# shield_mega_seed4_mpu_lobo8.net
KiCad netlist of a schematic drawn in EAGLE
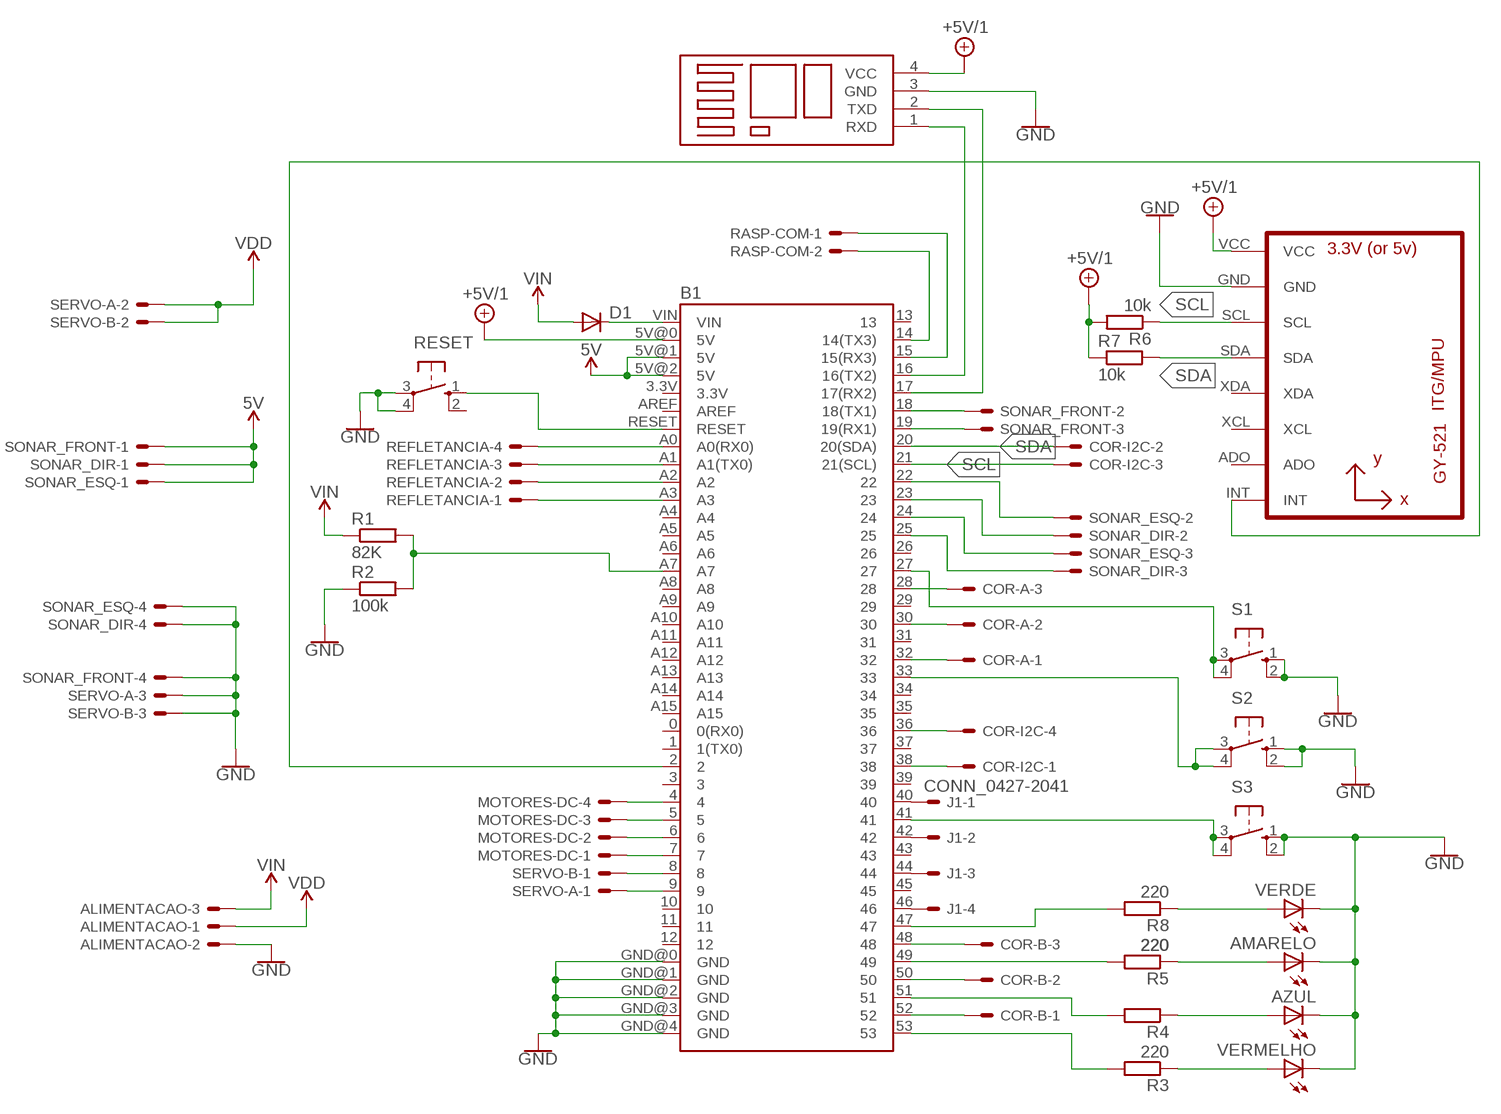
[diagram p0: schematic, sheet 1]

(export (version "E")
  (design (tool "Eeschema 10.0.6"))
  (components
    (comp (ref "ALIMENTACAO")
      (value "22-23-2031")
      (footprint "eagle-import:22-23-2031")
      (fields (field (name "MF") "MOLEX"))
      (libsource (lib "eagle-import") (part "22-23-2031"))
    )
    (comp (ref "AMARELO")
      (value "LED5MM")
      (footprint "eagle-import:LED5MM")
      (libsource (lib "eagle-import") (part "LED5MM"))
    )
    (comp (ref "AZUL")
      (value "LED5MM")
      (footprint "eagle-import:LED5MM")
      (libsource (lib "eagle-import") (part "LED5MM"))
    )
    (comp (ref "B1")
      (value "ARDUINO_MEGA_R3FULL")
      (footprint "eagle-import:ARDUINO_MEGA")
      (libsource (lib "eagle-import") (part "ARDUINO_MEGA_R3FULL"))
    )
    (comp (ref "B2")
      (value "BLUETOOTH")
      (footprint "eagle-import:BLUETOOTH")
      (libsource (lib "eagle-import") (part "BLUETOOTH"))
    )
    (comp (ref "COR-A")
      (value "22-23-2031")
      (footprint "eagle-import:22-23-2031")
      (fields (field (name "MF") "MOLEX"))
      (libsource (lib "eagle-import") (part "22-23-2031"))
    )
    (comp (ref "COR-B")
      (value "22-23-2031")
      (footprint "eagle-import:22-23-2031")
      (fields (field (name "MF") "MOLEX"))
      (libsource (lib "eagle-import") (part "22-23-2031"))
    )
    (comp (ref "COR-I2C")
      (value "22-23-2041")
      (footprint "eagle-import:22-23-2041")
      (fields (field (name "MF") "MOLEX"))
      (libsource (lib "eagle-import") (part "22-23-2041"))
    )
    (comp (ref "D1")
      (value "1N4004")
      (footprint "eagle-import:DO41-10")
      (libsource (lib "eagle-import") (part "1N4004"))
    )
    (comp (ref "J1")
      (value "CONN_0427-2041")
      (footprint "eagle-import:6410-04")
      (libsource (lib "eagle-import") (part "CONN_0427-2041"))
    )
    (comp (ref "MOTORES-DC")
      (value "22-23-2041")
      (footprint "eagle-import:22-23-2041")
      (fields (field (name "MF") "MOLEX"))
      (libsource (lib "eagle-import") (part "22-23-2041"))
    )
    (comp (ref "R1")
      (value "82K")
      (footprint "eagle-import:0204_7")
      (libsource (lib "eagle-import") (part "R-EU_0204/7"))
    )
    (comp (ref "R2")
      (value "100k")
      (footprint "eagle-import:0204_7")
      (libsource (lib "eagle-import") (part "R-EU_0204/7"))
    )
    (comp (ref "R3")
      (value "220")
      (footprint "eagle-import:0207_7")
      (libsource (lib "eagle-import") (part "R-EU_0207/7"))
    )
    (comp (ref "R4")
      (value "220")
      (footprint "eagle-import:0207_7")
      (libsource (lib "eagle-import") (part "R-EU_0207/7"))
    )
    (comp (ref "R5")
      (value "220")
      (footprint "eagle-import:0207_7")
      (libsource (lib "eagle-import") (part "R-EU_0207/7"))
    )
    (comp (ref "R6")
      (value "10k")
      (footprint "eagle-import:0204_7")
      (libsource (lib "eagle-import") (part "R-EU_0204/7"))
    )
    (comp (ref "R7")
      (value "10k")
      (footprint "eagle-import:0204_7")
      (libsource (lib "eagle-import") (part "R-EU_0204/7"))
    )
    (comp (ref "R8")
      (value "220")
      (footprint "eagle-import:0207_7")
      (libsource (lib "eagle-import") (part "R-EU_0207/7"))
    )
    (comp (ref "RASP-COM")
      (value "22-23-2021")
      (footprint "eagle-import:22-23-2021")
      (fields (field (name "MF") "MOLEX"))
      (libsource (lib "eagle-import") (part "22-23-2021"))
    )
    (comp (ref "REFLETANCIA")
      (value "22-23-2041")
      (footprint "eagle-import:22-23-2041")
      (fields (field (name "MF") "MOLEX"))
      (libsource (lib "eagle-import") (part "22-23-2041"))
    )
    (comp (ref "RESET")
      (value "10-XX")
      (footprint "eagle-import:B3F-10XX")
      (fields (field (name "MPN") "B3F-1000"))
      (libsource (lib "eagle-import") (part "10-XX"))
    )
    (comp (ref "S1")
      (value "10-XX")
      (footprint "eagle-import:B3F-10XX")
      (fields (field (name "MPN") "B3F-1000"))
      (libsource (lib "eagle-import") (part "10-XX"))
    )
    (comp (ref "S2")
      (value "10-XX")
      (footprint "eagle-import:B3F-10XX")
      (fields (field (name "MPN") "B3F-1000"))
      (libsource (lib "eagle-import") (part "10-XX"))
    )
    (comp (ref "S3")
      (value "10-XX")
      (footprint "eagle-import:B3F-10XX")
      (fields (field (name "MPN") "B3F-1000"))
      (libsource (lib "eagle-import") (part "10-XX"))
    )
    (comp (ref "SERVO-A")
      (value "22-23-2031")
      (footprint "eagle-import:22-23-2031")
      (fields (field (name "MF") "MOLEX"))
      (libsource (lib "eagle-import") (part "22-23-2031"))
    )
    (comp (ref "SERVO-B")
      (value "22-23-2031")
      (footprint "eagle-import:22-23-2031")
      (fields (field (name "MF") "MOLEX"))
      (libsource (lib "eagle-import") (part "22-23-2031"))
    )
    (comp (ref "SONAR_DIR")
      (value "22-23-2041")
      (footprint "eagle-import:22-23-2041")
      (fields (field (name "MF") "MOLEX"))
      (libsource (lib "eagle-import") (part "22-23-2041"))
    )
    (comp (ref "SONAR_ESQ")
      (value "22-23-2041")
      (footprint "eagle-import:22-23-2041")
      (fields (field (name "MF") "MOLEX"))
      (libsource (lib "eagle-import") (part "22-23-2041"))
    )
    (comp (ref "SONAR_FRONT")
      (value "22-23-2041")
      (footprint "eagle-import:22-23-2041")
      (fields (field (name "MF") "MOLEX"))
      (libsource (lib "eagle-import") (part "22-23-2041"))
    )
    (comp (ref "U1")
      (value "GY-521MPU6050")
      (footprint "eagle-import:GY-521")
      (libsource (lib "eagle-import") (part "GY-521MPU6050"))
    )
    (comp (ref "VERDE")
      (value "LED5MM")
      (footprint "eagle-import:LED5MM")
      (libsource (lib "eagle-import") (part "LED5MM"))
    )
    (comp (ref "VERMELHO")
      (value "LED5MM")
      (footprint "eagle-import:LED5MM")
      (libsource (lib "eagle-import") (part "LED5MM"))
    )
  )
  (nets
    (net (code "1") (name "+5V{slash}1") (class "Default")
      (node (ref "B1") (pin "5V@0") (pinfunction "5V_5V@0") (pintype "bidirectional"))
      (node (ref "B2") (pin "4") (pinfunction "VCC_4") (pintype "power_in"))
      (node (ref "R6") (pin "2") (pinfunction "2_2") (pintype "passive"))
      (node (ref "R7") (pin "1") (pinfunction "1_1") (pintype "passive"))
      (node (ref "U1") (pin "VCC") (pinfunction "VCC_VCC") (pintype "bidirectional"))
    )
    (net (code "2") (name "5V") (class "Default")
      (node (ref "B1") (pin "5V@1") (pinfunction "5V_5V@1") (pintype "bidirectional"))
      (node (ref "B1") (pin "5V@2") (pinfunction "5V_5V@2") (pintype "bidirectional"))
      (node (ref "SONAR_DIR") (pin "1") (pinfunction "S_1") (pintype "passive"))
      (node (ref "SONAR_ESQ") (pin "1") (pinfunction "S_1") (pintype "passive"))
      (node (ref "SONAR_FRONT") (pin "1") (pinfunction "S_1") (pintype "passive"))
    )
    (net (code "3") (name "GND") (class "Default")
      (node (ref "ALIMENTACAO") (pin "2") (pinfunction "S_2") (pintype "passive"))
      (node (ref "AMARELO") (pin "K") (pinfunction "C_K") (pintype "passive"))
      (node (ref "AZUL") (pin "K") (pinfunction "C_K") (pintype "passive"))
      (node (ref "B1") (pin "GND@0") (pinfunction "GND_GND@0") (pintype "bidirectional"))
      (node (ref "B1") (pin "GND@1") (pinfunction "GND_GND@1") (pintype "bidirectional"))
      (node (ref "B1") (pin "GND@2") (pinfunction "GND_GND@2") (pintype "bidirectional"))
      (node (ref "B1") (pin "GND@3") (pinfunction "GND_GND@3") (pintype "bidirectional"))
      (node (ref "B1") (pin "GND@4") (pinfunction "GND_GND@4") (pintype "bidirectional"))
      (node (ref "B2") (pin "3") (pinfunction "GND_3") (pintype "power_in"))
      (node (ref "R2") (pin "1") (pinfunction "1_1") (pintype "passive"))
      (node (ref "RESET") (pin "3") (pinfunction "P_3") (pintype "passive"))
      (node (ref "RESET") (pin "4") (pinfunction "P1_4") (pintype "passive"))
      (node (ref "S1") (pin "1") (pinfunction "S_1") (pintype "passive"))
      (node (ref "S1") (pin "2") (pinfunction "S1_2") (pintype "passive"))
      (node (ref "S2") (pin "1") (pinfunction "S_1") (pintype "passive"))
      (node (ref "S2") (pin "2") (pinfunction "S1_2") (pintype "passive"))
      (node (ref "S3") (pin "1") (pinfunction "S_1") (pintype "passive"))
      (node (ref "S3") (pin "2") (pinfunction "S1_2") (pintype "passive"))
      (node (ref "SERVO-A") (pin "3") (pinfunction "S_3") (pintype "passive"))
      (node (ref "SERVO-B") (pin "3") (pinfunction "S_3") (pintype "passive"))
      (node (ref "SONAR_DIR") (pin "4") (pinfunction "S_4") (pintype "passive"))
      (node (ref "SONAR_ESQ") (pin "4") (pinfunction "S_4") (pintype "passive"))
      (node (ref "SONAR_FRONT") (pin "4") (pinfunction "S_4") (pintype "passive"))
      (node (ref "U1") (pin "GND") (pinfunction "GND_GND") (pintype "bidirectional"))
      (node (ref "VERDE") (pin "K") (pinfunction "C_K") (pintype "passive"))
      (node (ref "VERMELHO") (pin "K") (pinfunction "C_K") (pintype "passive"))
    )
    (net (code "4") (name "Net-(AMARELO-PadA)") (class "Default")
      (node (ref "AMARELO") (pin "A") (pinfunction "A_A") (pintype "passive"))
      (node (ref "R5") (pin "1") (pinfunction "1_1") (pintype "passive"))
    )
    (net (code "5") (name "Net-(AZUL-PadA)") (class "Default")
      (node (ref "AZUL") (pin "A") (pinfunction "A_A") (pintype "passive"))
      (node (ref "R4") (pin "1") (pinfunction "1_1") (pintype "passive"))
    )
    (net (code "6") (name "Net-(B1-14(TX3))") (class "Default")
      (node (ref "B1") (pin "14") (pinfunction "14(TX3)_14") (pintype "bidirectional"))
      (node (ref "RASP-COM") (pin "2") (pinfunction "S_2") (pintype "passive"))
    )
    (net (code "7") (name "Net-(B1-15(RX3))") (class "Default")
      (node (ref "B1") (pin "15") (pinfunction "15(RX3)_15") (pintype "bidirectional"))
      (node (ref "RASP-COM") (pin "1") (pinfunction "S_1") (pintype "passive"))
    )
    (net (code "8") (name "Net-(B1-16(TX2))") (class "Default")
      (node (ref "B1") (pin "16") (pinfunction "16(TX2)_16") (pintype "bidirectional"))
      (node (ref "B2") (pin "1") (pinfunction "RXD_1") (pintype "bidirectional"))
    )
    (net (code "9") (name "Net-(B1-17(RX2))") (class "Default")
      (node (ref "B1") (pin "17") (pinfunction "17(RX2)_17") (pintype "bidirectional"))
      (node (ref "B2") (pin "2") (pinfunction "TXD_2") (pintype "bidirectional"))
    )
    (net (code "10") (name "Net-(B1-18(TX1))") (class "Default")
      (node (ref "B1") (pin "18") (pinfunction "18(TX1)_18") (pintype "bidirectional"))
      (node (ref "SONAR_FRONT") (pin "2") (pinfunction "S_2") (pintype "passive"))
    )
    (net (code "11") (name "Net-(B1-19(RX1))") (class "Default")
      (node (ref "B1") (pin "19") (pinfunction "19(RX1)_19") (pintype "bidirectional"))
      (node (ref "SONAR_FRONT") (pin "3") (pinfunction "S_3") (pintype "passive"))
    )
    (net (code "12") (name "Net-(B1-A0(RX0))") (class "Default")
      (node (ref "B1") (pin "A0") (pinfunction "A0(RX0)_A0") (pintype "bidirectional"))
      (node (ref "REFLETANCIA") (pin "4") (pinfunction "S_4") (pintype "passive"))
    )
    (net (code "13") (name "Net-(B1-A1(TX0))") (class "Default")
      (node (ref "B1") (pin "A1") (pinfunction "A1(TX0)_A1") (pintype "bidirectional"))
      (node (ref "REFLETANCIA") (pin "3") (pinfunction "S_3") (pintype "passive"))
    )
    (net (code "14") (name "Net-(B1-Pad2)") (class "Default")
      (node (ref "B1") (pin "2") (pinfunction "2_2") (pintype "bidirectional"))
      (node (ref "U1") (pin "INT") (pinfunction "INT_INT") (pintype "bidirectional"))
    )
    (net (code "15") (name "Net-(B1-Pad47)") (class "Default")
      (node (ref "B1") (pin "47") (pinfunction "47_47") (pintype "bidirectional"))
      (node (ref "R8") (pin "2") (pinfunction "2_2") (pintype "passive"))
    )
    (net (code "16") (name "Net-(B1-Pad49)") (class "Default")
      (node (ref "B1") (pin "49") (pinfunction "49_49") (pintype "bidirectional"))
      (node (ref "R5") (pin "2") (pinfunction "2_2") (pintype "passive"))
    )
    (net (code "17") (name "Net-(B1-Pad51)") (class "Default")
      (node (ref "B1") (pin "51") (pinfunction "51_51") (pintype "bidirectional"))
      (node (ref "R4") (pin "2") (pinfunction "2_2") (pintype "passive"))
    )
    (net (code "18") (name "Net-(B1-Pad53)") (class "Default")
      (node (ref "B1") (pin "53") (pinfunction "53_53") (pintype "bidirectional"))
      (node (ref "R3") (pin "2") (pinfunction "2_2") (pintype "passive"))
    )
    (net (code "19") (name "Net-(B1-PadA7)") (class "Default")
      (node (ref "B1") (pin "A7") (pinfunction "A7_A7") (pintype "bidirectional"))
      (node (ref "R1") (pin "2") (pinfunction "2_2") (pintype "passive"))
      (node (ref "R2") (pin "2") (pinfunction "2_2") (pintype "passive"))
    )
    (net (code "20") (name "Net-(B1-PadVIN)") (class "Default")
      (node (ref "B1") (pin "VIN") (pinfunction "VIN_VIN") (pintype "bidirectional"))
      (node (ref "D1") (pin "C") (pinfunction "C_C") (pintype "passive"))
    )
    (net (code "21") (name "Net-(COR-AA-S)") (class "Default")
      (node (ref "B1") (pin "32") (pinfunction "32_32") (pintype "bidirectional"))
      (node (ref "COR-A") (pin "1") (pinfunction "S_1") (pintype "passive"))
    )
    (net (code "22") (name "Net-(COR-AB-S)") (class "Default")
      (node (ref "B1") (pin "30") (pinfunction "30_30") (pintype "bidirectional"))
      (node (ref "COR-A") (pin "2") (pinfunction "S_2") (pintype "passive"))
    )
    (net (code "23") (name "Net-(COR-AC-S)") (class "Default")
      (node (ref "B1") (pin "28") (pinfunction "28_28") (pintype "bidirectional"))
      (node (ref "COR-A") (pin "3") (pinfunction "S_3") (pintype "passive"))
    )
    (net (code "24") (name "Net-(COR-BA-S)") (class "Default")
      (node (ref "B1") (pin "52") (pinfunction "52_52") (pintype "bidirectional"))
      (node (ref "COR-B") (pin "1") (pinfunction "S_1") (pintype "passive"))
    )
    (net (code "25") (name "Net-(COR-BB-S)") (class "Default")
      (node (ref "B1") (pin "50") (pinfunction "50_50") (pintype "bidirectional"))
      (node (ref "COR-B") (pin "2") (pinfunction "S_2") (pintype "passive"))
    )
    (net (code "26") (name "Net-(COR-BC-S)") (class "Default")
      (node (ref "B1") (pin "48") (pinfunction "48_48") (pintype "bidirectional"))
      (node (ref "COR-B") (pin "3") (pinfunction "S_3") (pintype "passive"))
    )
    (net (code "27") (name "Net-(COR-I2CA-S)") (class "Default")
      (node (ref "B1") (pin "38") (pinfunction "38_38") (pintype "bidirectional"))
      (node (ref "COR-I2C") (pin "1") (pinfunction "S_1") (pintype "passive"))
    )
    (net (code "28") (name "Net-(COR-I2CD-S)") (class "Default")
      (node (ref "B1") (pin "36") (pinfunction "36_36") (pintype "bidirectional"))
      (node (ref "COR-I2C") (pin "4") (pinfunction "S_4") (pintype "passive"))
    )
    (net (code "29") (name "Net-(J1A-S)") (class "Default")
      (node (ref "B1") (pin "40") (pinfunction "40_40") (pintype "bidirectional"))
      (node (ref "J1") (pin "1") (pinfunction "S_1") (pintype "passive"))
    )
    (net (code "30") (name "Net-(J1B-S)") (class "Default")
      (node (ref "B1") (pin "42") (pinfunction "42_42") (pintype "bidirectional"))
      (node (ref "J1") (pin "2") (pinfunction "S_2") (pintype "passive"))
    )
    (net (code "31") (name "Net-(J1C-S)") (class "Default")
      (node (ref "B1") (pin "44") (pinfunction "44_44") (pintype "bidirectional"))
      (node (ref "J1") (pin "3") (pinfunction "S_3") (pintype "passive"))
    )
    (net (code "32") (name "Net-(J1D-S)") (class "Default")
      (node (ref "B1") (pin "46") (pinfunction "46_46") (pintype "bidirectional"))
      (node (ref "J1") (pin "4") (pinfunction "S_4") (pintype "passive"))
    )
    (net (code "33") (name "Net-(MOTORES-DCA-S)") (class "Default")
      (node (ref "B1") (pin "7") (pinfunction "7_7") (pintype "bidirectional"))
      (node (ref "MOTORES-DC") (pin "1") (pinfunction "S_1") (pintype "passive"))
    )
    (net (code "34") (name "Net-(MOTORES-DCB-S)") (class "Default")
      (node (ref "B1") (pin "6") (pinfunction "6_6") (pintype "bidirectional"))
      (node (ref "MOTORES-DC") (pin "2") (pinfunction "S_2") (pintype "passive"))
    )
    (net (code "35") (name "Net-(MOTORES-DCC-S)") (class "Default")
      (node (ref "B1") (pin "5") (pinfunction "5_5") (pintype "bidirectional"))
      (node (ref "MOTORES-DC") (pin "3") (pinfunction "S_3") (pintype "passive"))
    )
    (net (code "36") (name "Net-(MOTORES-DCD-S)") (class "Default")
      (node (ref "B1") (pin "4") (pinfunction "4_4") (pintype "bidirectional"))
      (node (ref "MOTORES-DC") (pin "4") (pinfunction "S_4") (pintype "passive"))
    )
    (net (code "37") (name "Net-(R3-Pad1)") (class "Default")
      (node (ref "R3") (pin "1") (pinfunction "1_1") (pintype "passive"))
      (node (ref "VERMELHO") (pin "A") (pinfunction "A_A") (pintype "passive"))
    )
    (net (code "38") (name "Net-(R8-Pad1)") (class "Default")
      (node (ref "R8") (pin "1") (pinfunction "1_1") (pintype "passive"))
      (node (ref "VERDE") (pin "A") (pinfunction "A_A") (pintype "passive"))
    )
    (net (code "39") (name "Net-(REFLETANCIAA-S)") (class "Default")
      (node (ref "B1") (pin "A3") (pinfunction "A3_A3") (pintype "bidirectional"))
      (node (ref "REFLETANCIA") (pin "1") (pinfunction "S_1") (pintype "passive"))
    )
    (net (code "40") (name "Net-(REFLETANCIAB-S)") (class "Default")
      (node (ref "B1") (pin "A2") (pinfunction "A2_A2") (pintype "bidirectional"))
      (node (ref "REFLETANCIA") (pin "2") (pinfunction "S_2") (pintype "passive"))
    )
    (net (code "41") (name "Net-(RESET-S)") (class "Default")
      (node (ref "B1") (pin "RESET") (pinfunction "RESET_RESET") (pintype "bidirectional"))
      (node (ref "RESET") (pin "1") (pinfunction "S_1") (pintype "passive"))
    )
    (net (code "42") (name "Net-(S1-P)") (class "Default")
      (node (ref "B1") (pin "27") (pinfunction "27_27") (pintype "bidirectional"))
      (node (ref "S1") (pin "3") (pinfunction "P_3") (pintype "passive"))
      (node (ref "S1") (pin "4") (pinfunction "P1_4") (pintype "passive"))
    )
    (net (code "43") (name "Net-(S2-P)") (class "Default")
      (node (ref "B1") (pin "33") (pinfunction "33_33") (pintype "bidirectional"))
      (node (ref "S2") (pin "3") (pinfunction "P_3") (pintype "passive"))
      (node (ref "S2") (pin "4") (pinfunction "P1_4") (pintype "passive"))
    )
    (net (code "44") (name "Net-(S3-P)") (class "Default")
      (node (ref "B1") (pin "41") (pinfunction "41_41") (pintype "bidirectional"))
      (node (ref "S3") (pin "3") (pinfunction "P_3") (pintype "passive"))
      (node (ref "S3") (pin "4") (pinfunction "P1_4") (pintype "passive"))
    )
    (net (code "45") (name "Net-(SERVO-AA-S)") (class "Default")
      (node (ref "B1") (pin "9") (pinfunction "9_9") (pintype "bidirectional"))
      (node (ref "SERVO-A") (pin "1") (pinfunction "S_1") (pintype "passive"))
    )
    (net (code "46") (name "Net-(SERVO-BA-S)") (class "Default")
      (node (ref "B1") (pin "8") (pinfunction "8_8") (pintype "bidirectional"))
      (node (ref "SERVO-B") (pin "1") (pinfunction "S_1") (pintype "passive"))
    )
    (net (code "47") (name "Net-(SONAR_DIRB-S)") (class "Default")
      (node (ref "B1") (pin "23") (pinfunction "23_23") (pintype "bidirectional"))
      (node (ref "SONAR_DIR") (pin "2") (pinfunction "S_2") (pintype "passive"))
    )
    (net (code "48") (name "Net-(SONAR_DIRC-S)") (class "Default")
      (node (ref "B1") (pin "25") (pinfunction "25_25") (pintype "bidirectional"))
      (node (ref "SONAR_DIR") (pin "3") (pinfunction "S_3") (pintype "passive"))
    )
    (net (code "49") (name "Net-(SONAR_ESQB-S)") (class "Default")
      (node (ref "B1") (pin "22") (pinfunction "22_22") (pintype "bidirectional"))
      (node (ref "SONAR_ESQ") (pin "2") (pinfunction "S_2") (pintype "passive"))
    )
    (net (code "50") (name "Net-(SONAR_ESQC-S)") (class "Default")
      (node (ref "B1") (pin "24") (pinfunction "24_24") (pintype "bidirectional"))
      (node (ref "SONAR_ESQ") (pin "3") (pinfunction "S_3") (pintype "passive"))
    )
    (net (code "51") (name "SCL") (class "Default")
      (node (ref "B1") (pin "21") (pinfunction "21(SCL)_21") (pintype "bidirectional"))
      (node (ref "COR-I2C") (pin "3") (pinfunction "S_3") (pintype "passive"))
      (node (ref "R6") (pin "1") (pinfunction "1_1") (pintype "passive"))
      (node (ref "U1") (pin "SCL") (pinfunction "SCL_SCL") (pintype "bidirectional"))
    )
    (net (code "52") (name "SDA") (class "Default")
      (node (ref "B1") (pin "20") (pinfunction "20(SDA)_20") (pintype "bidirectional"))
      (node (ref "COR-I2C") (pin "2") (pinfunction "S_2") (pintype "passive"))
      (node (ref "R7") (pin "2") (pinfunction "2_2") (pintype "passive"))
      (node (ref "U1") (pin "SDA") (pinfunction "SDA_SDA") (pintype "bidirectional"))
    )
    (net (code "53") (name "VDD") (class "Default")
      (node (ref "ALIMENTACAO") (pin "1") (pinfunction "S_1") (pintype "passive"))
      (node (ref "SERVO-A") (pin "2") (pinfunction "S_2") (pintype "passive"))
      (node (ref "SERVO-B") (pin "2") (pinfunction "S_2") (pintype "passive"))
    )
    (net (code "54") (name "VIN") (class "Default")
      (node (ref "ALIMENTACAO") (pin "3") (pinfunction "S_3") (pintype "passive"))
      (node (ref "D1") (pin "A") (pinfunction "A_A") (pintype "passive"))
      (node (ref "R1") (pin "1") (pinfunction "1_1") (pintype "passive"))
    )
    (net (code "55") (name "unconnected-(B1-0(RX0)-Pad0)") (class "Default")
      (node (ref "B1") (pin "0") (pinfunction "0(RX0)_0") (pintype "bidirectional"))
    )
    (net (code "56") (name "unconnected-(B1-1(TX0)-Pad1)") (class "Default")
      (node (ref "B1") (pin "1") (pinfunction "1(TX0)_1") (pintype "bidirectional"))
    )
    (net (code "57") (name "unconnected-(B1-Pad3)") (class "Default")
      (node (ref "B1") (pin "3") (pinfunction "3_3") (pintype "bidirectional"))
    )
    (net (code "58") (name "unconnected-(B1-Pad3.3V)") (class "Default")
      (node (ref "B1") (pin "3.3V") (pinfunction "3.3V_3.3V") (pintype "bidirectional"))
    )
    (net (code "59") (name "unconnected-(B1-Pad10)") (class "Default")
      (node (ref "B1") (pin "10") (pinfunction "10_10") (pintype "bidirectional"))
    )
    (net (code "60") (name "unconnected-(B1-Pad11)") (class "Default")
      (node (ref "B1") (pin "11") (pinfunction "11_11") (pintype "bidirectional"))
    )
    (net (code "61") (name "unconnected-(B1-Pad12)") (class "Default")
      (node (ref "B1") (pin "12") (pinfunction "12_12") (pintype "bidirectional"))
    )
    (net (code "62") (name "unconnected-(B1-Pad13)") (class "Default")
      (node (ref "B1") (pin "13") (pinfunction "13_13") (pintype "bidirectional"))
    )
    (net (code "63") (name "unconnected-(B1-Pad26)") (class "Default")
      (node (ref "B1") (pin "26") (pinfunction "26_26") (pintype "bidirectional"))
    )
    (net (code "64") (name "unconnected-(B1-Pad29)") (class "Default")
      (node (ref "B1") (pin "29") (pinfunction "29_29") (pintype "bidirectional"))
    )
    (net (code "65") (name "unconnected-(B1-Pad31)") (class "Default")
      (node (ref "B1") (pin "31") (pinfunction "31_31") (pintype "bidirectional"))
    )
    (net (code "66") (name "unconnected-(B1-Pad34)") (class "Default")
      (node (ref "B1") (pin "34") (pinfunction "34_34") (pintype "bidirectional"))
    )
    (net (code "67") (name "unconnected-(B1-Pad35)") (class "Default")
      (node (ref "B1") (pin "35") (pinfunction "35_35") (pintype "bidirectional"))
    )
    (net (code "68") (name "unconnected-(B1-Pad37)") (class "Default")
      (node (ref "B1") (pin "37") (pinfunction "37_37") (pintype "bidirectional"))
    )
    (net (code "69") (name "unconnected-(B1-Pad39)") (class "Default")
      (node (ref "B1") (pin "39") (pinfunction "39_39") (pintype "bidirectional"))
    )
    (net (code "70") (name "unconnected-(B1-Pad43)") (class "Default")
      (node (ref "B1") (pin "43") (pinfunction "43_43") (pintype "bidirectional"))
    )
    (net (code "71") (name "unconnected-(B1-Pad45)") (class "Default")
      (node (ref "B1") (pin "45") (pinfunction "45_45") (pintype "bidirectional"))
    )
    (net (code "72") (name "unconnected-(B1-PadA4)") (class "Default")
      (node (ref "B1") (pin "A4") (pinfunction "A4_A4") (pintype "bidirectional"))
    )
    (net (code "73") (name "unconnected-(B1-PadA5)") (class "Default")
      (node (ref "B1") (pin "A5") (pinfunction "A5_A5") (pintype "bidirectional"))
    )
    (net (code "74") (name "unconnected-(B1-PadA6)") (class "Default")
      (node (ref "B1") (pin "A6") (pinfunction "A6_A6") (pintype "bidirectional"))
    )
    (net (code "75") (name "unconnected-(B1-PadA8)") (class "Default")
      (node (ref "B1") (pin "A8") (pinfunction "A8_A8") (pintype "bidirectional"))
    )
    (net (code "76") (name "unconnected-(B1-PadA9)") (class "Default")
      (node (ref "B1") (pin "A9") (pinfunction "A9_A9") (pintype "bidirectional"))
    )
    (net (code "77") (name "unconnected-(B1-PadA10)") (class "Default")
      (node (ref "B1") (pin "A10") (pinfunction "A10_A10") (pintype "bidirectional"))
    )
    (net (code "78") (name "unconnected-(B1-PadA11)") (class "Default")
      (node (ref "B1") (pin "A11") (pinfunction "A11_A11") (pintype "bidirectional"))
    )
    (net (code "79") (name "unconnected-(B1-PadA12)") (class "Default")
      (node (ref "B1") (pin "A12") (pinfunction "A12_A12") (pintype "bidirectional"))
    )
    (net (code "80") (name "unconnected-(B1-PadA13)") (class "Default")
      (node (ref "B1") (pin "A13") (pinfunction "A13_A13") (pintype "bidirectional"))
    )
    (net (code "81") (name "unconnected-(B1-PadA14)") (class "Default")
      (node (ref "B1") (pin "A14") (pinfunction "A14_A14") (pintype "bidirectional"))
    )
    (net (code "82") (name "unconnected-(B1-PadA15)") (class "Default")
      (node (ref "B1") (pin "A15") (pinfunction "A15_A15") (pintype "bidirectional"))
    )
    (net (code "83") (name "unconnected-(B1-PadAREF)") (class "Default")
      (node (ref "B1") (pin "AREF") (pinfunction "AREF_AREF") (pintype "bidirectional"))
    )
    (net (code "84") (name "unconnected-(RESET-S1-Pad2)") (class "Default")
      (node (ref "RESET") (pin "2") (pinfunction "S1_2") (pintype "passive"))
    )
    (net (code "85") (name "unconnected-(U1-PadADO)") (class "Default")
      (node (ref "U1") (pin "ADO") (pinfunction "ADO_ADO") (pintype "bidirectional"))
    )
    (net (code "86") (name "unconnected-(U1-PadXCL)") (class "Default")
      (node (ref "U1") (pin "XCL") (pinfunction "XCL_XCL") (pintype "bidirectional"))
    )
    (net (code "87") (name "unconnected-(U1-PadXDA)") (class "Default")
      (node (ref "U1") (pin "XDA") (pinfunction "XDA_XDA") (pintype "bidirectional"))
    )
  )
)
